# guangshan.net
KiCad netlist of a schematic drawn in EasyEDA Pro
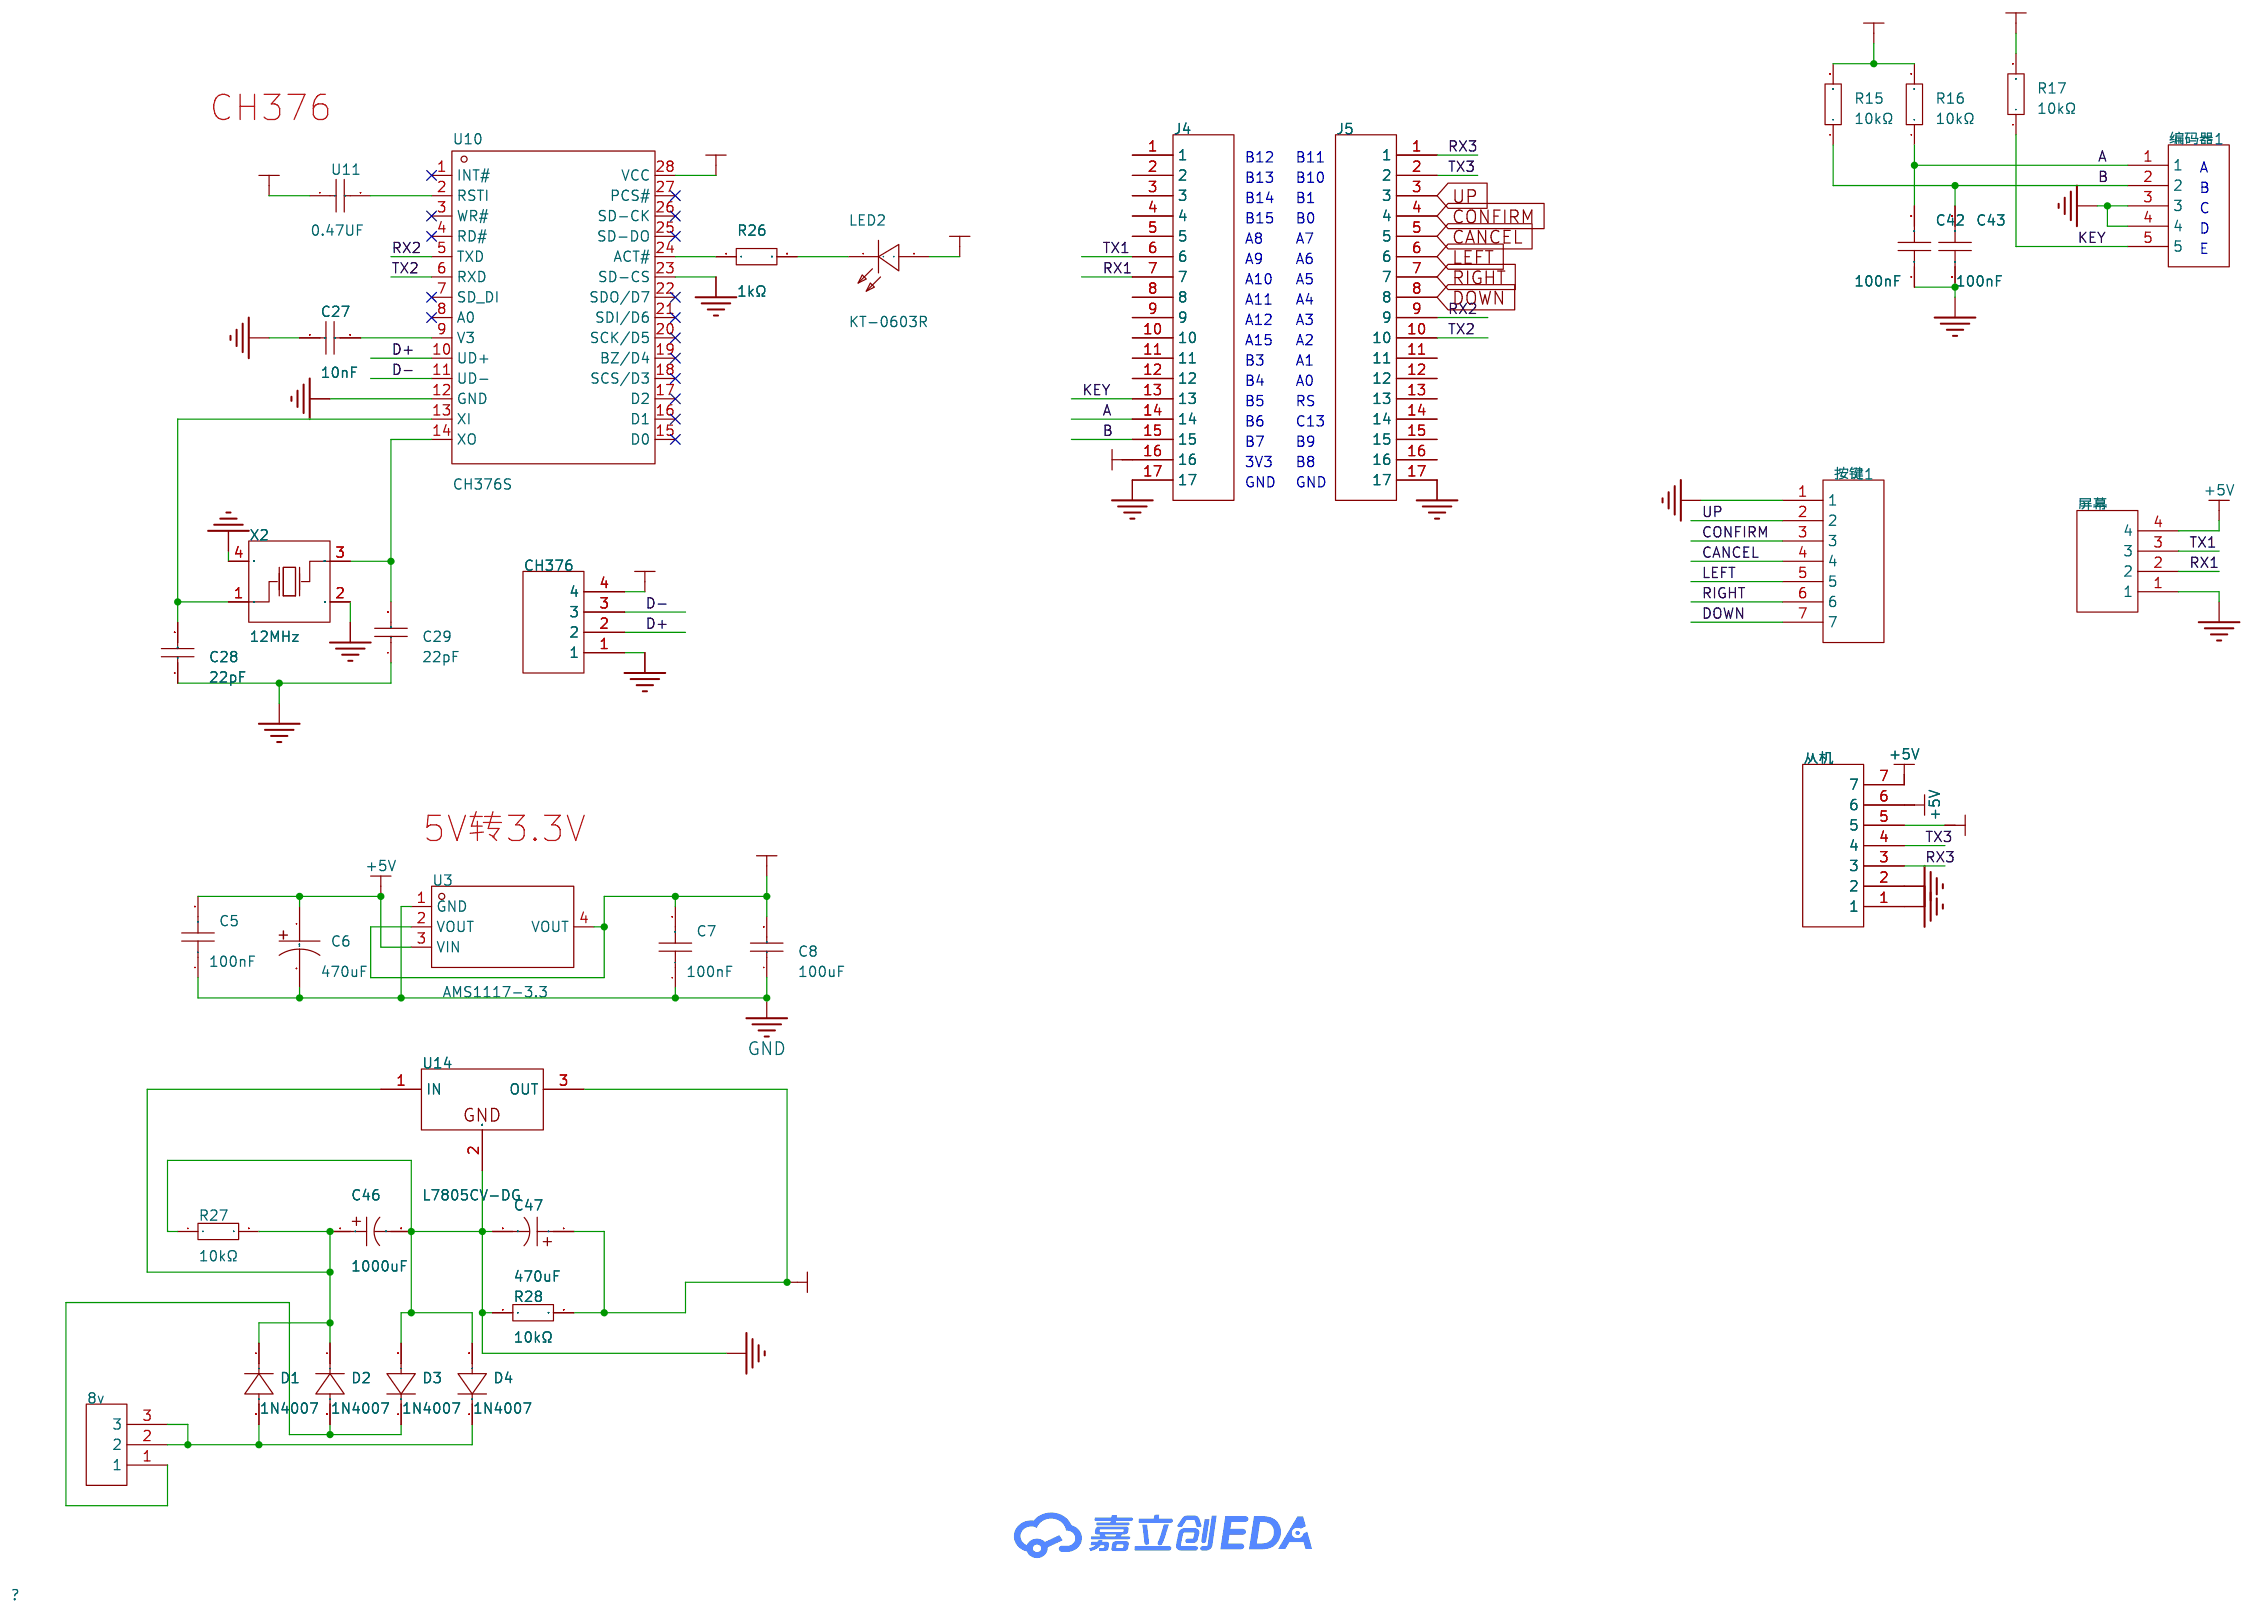
[diagram p0: schematic sheet]

(export (version "E")
  (design (tool "Eeschema 10.0.6"))
  (components
    (comp (ref "8v")
      (value "~")
      (footprint "easyedapro:CH2.54-3插座")
      (libsource (lib "easyedapro") (part "HDR-3P"))
    )
    (comp (ref "C5")
      (value "100nF")
      (footprint "easyedapro:C0603")
      (libsource (lib "easyedapro") (part "CapAcitance"))
    )
    (comp (ref "C6")
      (value "470uF")
      (footprint "easyedapro:CAP-SMD_BD6.3-L6.6-W6.6-FD")
      (description "容值:470uF;精度:±20%;额定电压:10V;纹波电流:200mA@120Hz;等效串联电阻:-;")
      (fields (field (name "Manufacturer Part") "RVT1A471M0607") (field (name "Manufacturer") "ROQANG(容强)"))
      (libsource (lib "easyedapro") (part "RVT1A471M0607_C335982"))
    )
    (comp (ref "C7")
      (value "100nF")
      (footprint "easyedapro:C0603")
      (libsource (lib "easyedapro") (part "CapAcitance"))
    )
    (comp (ref "C8")
      (value "100uF")
      (footprint "easyedapro:C1206")
      (description "容值:100uF;精度:±20%;额定电压:6.3V;材质(温度系数):X5R;")
      (fields
        (field (name "Manufacturer Part") "CL31A107MQHNNNE")
        (field (name "Manufacturer") "SAMSUNG(三星)")
      )
      (libsource (lib "easyedapro") (part "CL31A107MQHNNNE"))
    )
    (comp (ref "C27")
      (value "10nF")
      (footprint "easyedapro:C0603")
      (description "容值:10nF;精度:±10%;额定电压:50V;材质(温度系数):X7R;")
      (fields (field (name "Manufacturer Part") "0603B103K500NT") (field (name "Manufacturer") "FH(风华)"))
      (libsource (lib "easyedapro") (part "0603B103K500NT"))
    )
    (comp (ref "C28")
      (value "22pF")
      (footprint "easyedapro:C0603")
      (description "容值:22pF;精度:±5%;额定电压:50V;材质(温度系数):C0G;")
      (fields
        (field (name "Manufacturer Part") "CL10C220JB8NNNC")
        (field (name "Manufacturer") "SAMSUNG(三星)")
      )
      (libsource (lib "easyedapro") (part "CL10C220JB8NNNC"))
    )
    (comp (ref "C29")
      (value "22pF")
      (footprint "easyedapro:C0603")
      (description "容值:22pF;精度:±5%;额定电压:50V;材质(温度系数):C0G;")
      (fields
        (field (name "Manufacturer Part") "CL10C220JB8NNNC")
        (field (name "Manufacturer") "SAMSUNG(三星)")
      )
      (libsource (lib "easyedapro") (part "CL10C220JB8NNNC"))
    )
    (comp (ref "C42")
      (value "100nF")
      (footprint "easyedapro:C0402")
      (description "容值:100nF;精度:±10%;额定电压:50V;材质(温度系数):X7R;")
      (fields
        (field (name "Manufacturer Part") "CL05B104KB54PNC")
        (field (name "Manufacturer") "SAMSUNG(三星)")
      )
      (libsource (lib "easyedapro") (part "CL05B104KB54PNC"))
    )
    (comp (ref "C43")
      (value "100nF")
      (footprint "easyedapro:C0402")
      (description "容值:100nF;精度:±10%;额定电压:50V;材质(温度系数):X7R;")
      (fields
        (field (name "Manufacturer Part") "CL05B104KB54PNC")
        (field (name "Manufacturer") "SAMSUNG(三星)")
      )
      (libsource (lib "easyedapro") (part "CL05B104KB54PNC"))
    )
    (comp (ref "C46")
      (value "1000uF")
      (footprint "easyedapro:CAP-TH_BD10.0-P5.00-D0.6-FD")
      (description "容值:1000uF;额定电压:35V;")
      (fields
        (field (name "Manufacturer Part") "CD288108M1V1020VFL")
        (field (name "Manufacturer") "HRK(鸿瑞凯电子)")
      )
      (libsource (lib "easyedapro") (part "CD288108M1V1020VFL"))
    )
    (comp (ref "C47")
      (value "470uF")
      (footprint "easyedapro:CAP-TH_BD8.0-P3.50-D0.5-FD")
      (description "容值:470uF;精度:±20%;额定电压:16V;")
      (fields (field (name "Manufacturer Part") "16V470uF CD288") (field (name "Manufacturer") "HRK(鸿瑞凯电子)"))
      (libsource (lib "easyedapro") (part "16V470UF CD288"))
    )
    (comp (ref "CH376")
      (value "~")
      (footprint "easyedapro:CH2.54-4插座")
      (libsource (lib "easyedapro") (part "HDR-4P"))
    )
    (comp (ref "D1")
      (value "1N4007")
      (footprint "easyedapro:DO-41_BD2.4-L4.7-P8.70-D0.8-RD")
      (description "二极管配置:独立式;正向压降(Vf):1V@1A;直流反向耐压(Vr):1kV;整流电流:1A;")
      (fields (field (name "Manufacturer") "GOODWORK(固得沃克)"))
      (libsource (lib "easyedapro") (part "1N4007_C2985028"))
    )
    (comp (ref "D2")
      (value "1N4007")
      (footprint "easyedapro:DO-41_BD2.4-L4.7-P8.70-D0.8-RD")
      (description "二极管配置:独立式;正向压降(Vf):1V@1A;直流反向耐压(Vr):1kV;整流电流:1A;")
      (fields (field (name "Manufacturer") "GOODWORK(固得沃克)"))
      (libsource (lib "easyedapro") (part "1N4007_C2985028"))
    )
    (comp (ref "D3")
      (value "1N4007")
      (footprint "easyedapro:DO-41_BD2.4-L4.7-P8.70-D0.8-RD")
      (description "二极管配置:独立式;正向压降(Vf):1V@1A;直流反向耐压(Vr):1kV;整流电流:1A;")
      (fields (field (name "Manufacturer") "GOODWORK(固得沃克)"))
      (libsource (lib "easyedapro") (part "1N4007_C2985028"))
    )
    (comp (ref "D4")
      (value "1N4007")
      (footprint "easyedapro:DO-41_BD2.4-L4.7-P8.70-D0.8-RD")
      (description "二极管配置:独立式;正向压降(Vf):1V@1A;直流反向耐压(Vr):1kV;整流电流:1A;")
      (fields (field (name "Manufacturer") "GOODWORK(固得沃克)"))
      (libsource (lib "easyedapro") (part "1N4007_C2985028"))
    )
    (comp (ref "J4") (value "~") (libsource (lib "easyedapro") (part "HDR-17P")))
    (comp (ref "J5") (value "~") (libsource (lib "easyedapro") (part "HDR-17P")))
    (comp (ref "LED2")
      (value "KT-0603R")
      (footprint "easyedapro:LED0603-RD")
      (description "发光颜色:红色;功率:-;正向电流:-;主波长:-;二极管配置:-;透镜颜色:-;色温:-;发光角度:-;载带方式:-;工作温度:-40°C~+85°C;")
      (fields (field (name "Manufacturer") "KENTO"))
      (libsource (lib "easyedapro") (part "KT-0603R"))
    )
    (comp (ref "R15")
      (value "10kΩ")
      (footprint "easyedapro:R0805")
      (description "电阻类型:厚膜电阻;阻值:10kΩ;精度:±1%;功率:125mW;最大工作电压:150V;温度系数:±100ppm/°C;")
      (fields
        (field (name "Manufacturer Part") "0805W8F1002T5E")
        (field (name "Manufacturer") "UNI-ROYAL(厚声)")
      )
      (libsource (lib "easyedapro") (part "0805W8F1002T5E"))
    )
    (comp (ref "R16")
      (value "10kΩ")
      (footprint "easyedapro:R0805")
      (description "电阻类型:厚膜电阻;阻值:10kΩ;精度:±1%;功率:125mW;最大工作电压:150V;温度系数:±100ppm/°C;")
      (fields
        (field (name "Manufacturer Part") "0805W8F1002T5E")
        (field (name "Manufacturer") "UNI-ROYAL(厚声)")
      )
      (libsource (lib "easyedapro") (part "0805W8F1002T5E"))
    )
    (comp (ref "R17")
      (value "10kΩ")
      (footprint "easyedapro:R0805")
      (description "电阻类型:厚膜电阻;阻值:10kΩ;精度:±1%;功率:125mW;最大工作电压:150V;温度系数:±100ppm/°C;")
      (fields
        (field (name "Manufacturer Part") "0805W8F1002T5E")
        (field (name "Manufacturer") "UNI-ROYAL(厚声)")
      )
      (libsource (lib "easyedapro") (part "0805W8F1002T5E"))
    )
    (comp (ref "R26")
      (value "1kΩ")
      (footprint "easyedapro:R0603")
      (description "电阻类型:厚膜电阻;阻值:1kΩ;精度:±1%;功率:100mW;最大工作电压:75V;温度系数:±100ppm/°C;")
      (fields
        (field (name "Manufacturer Part") "0603WAF1001T5E")
        (field (name "Manufacturer") "UNI-ROYAL(厚声)")
      )
      (libsource (lib "easyedapro") (part "0603WAF1001T5E"))
    )
    (comp (ref "R27")
      (value "10kΩ")
      (footprint "easyedapro:R0603")
      (libsource (lib "easyedapro") (part "电阻"))
    )
    (comp (ref "R28")
      (value "10kΩ")
      (footprint "easyedapro:R0603")
      (libsource (lib "easyedapro") (part "电阻"))
    )
    (comp (ref "U3")
      (value "AMS1117-3.3")
      (footprint "easyedapro:SOT-223-3_L6.5-W3.4-P2.30-LS7.0-BR")
      (description "输出类型:固定;最大输入电压:-;输出电压:3.3V;最大输出电流:1A;电源纹波抑制比(PSRR):72dB@(120Hz);输出极性:正极;")
      (fields (field (name "Manufacturer") "AMS"))
      (libsource (lib "easyedapro") (part "AMS1117-3.3"))
    )
    (comp (ref "U10")
      (value "CH376S")
      (footprint "easyedapro:SOIC-28_L17.9-W7.5-P1.27-LS10.3-BL")
      (description "应用功能:-;接口协议:USB 2.0;数据速率:12Mbps;")
      (fields (field (name "Manufacturer") "WCH(南京沁恒)"))
      (libsource (lib "easyedapro") (part "CH376S"))
    )
    (comp (ref "U11")
      (value "0.47UF")
      (footprint "easyedapro:C0603")
      (libsource (lib "easyedapro") (part "CAPCER0.47UF25VX7R0603"))
    )
    (comp (ref "U14")
      (value "L7805CV-DG")
      (footprint "easyedapro:TO-220-3_L10.0-W4.5-P2.54-L")
      (description "输出类型:固定;最大输入电压:35V;输出电压:5V;输出电流:1.5A;电源纹波抑制比(PSRR):62dB@(120Hz);输出极性:正极;")
      (fields (field (name "Manufacturer") "ST(意法半导体)"))
      (libsource (lib "easyedapro") (part "L7805CV-DG"))
    )
    (comp (ref "X2")
      (value "12MHz")
      (footprint "easyedapro:CRYSTAL-SMD_4P-L3.2-W2.5-BL")
      (description "晶振类型:贴片晶振;频率:12MHz;常温频差:±10ppm;外接负载电容:20pF;频率稳定度(全温):±20ppm;")
      (fields (field (name "Manufacturer Part") "X322512MSB4SI") (field (name "Manufacturer") "YXC(扬兴晶振)"))
      (libsource (lib "easyedapro") (part "X322512MSB4SI"))
    )
    (comp (ref "从机")
      (value "~")
      (footprint "easyedapro:CH2.54-7插座")
      (libsource (lib "easyedapro") (part "HDR-7P"))
    )
    (comp (ref "屏幕")
      (value "~")
      (footprint "easyedapro:CH2.54-4插座")
      (libsource (lib "easyedapro") (part "HDR-4P"))
    )
    (comp (ref "按键1")
      (value "~")
      (footprint "easyedapro:CH2.54-7插座")
      (libsource (lib "easyedapro") (part "HDR-7P"))
    )
    (comp (ref "编码器1")
      (value "~")
      (footprint "easyedapro:CH2.54-5插座")
      (libsource (lib "easyedapro") (part "HDR-5P"))
    )
  )
  (nets
    (net (code "1") (name "+3V3") (class "Default")
      (node (ref "C7") (pin "2") (pinfunction "2_2") (pintype "input"))
      (node (ref "C8") (pin "2") (pinfunction "2_2") (pintype "input"))
      (node (ref "J4") (pin "16") (pinfunction "16_16") (pintype "input"))
      (node (ref "LED2") (pin "2") (pinfunction "A_2") (pintype "unspecified"))
      (node (ref "R15") (pin "2") (pinfunction "2_2") (pintype "input"))
      (node (ref "R16") (pin "2") (pinfunction "2_2") (pintype "input"))
      (node (ref "R17") (pin "2") (pinfunction "2_2") (pintype "input"))
      (node (ref "U10") (pin "28") (pinfunction "VCC_28") (pintype "unspecified"))
      (node (ref "U11") (pin "1") (pinfunction "1_1") (pintype "input"))
      (node (ref "U3") (pin "2") (pinfunction "VOUT_2") (pintype "unspecified"))
      (node (ref "U3") (pin "4") (pinfunction "VOUT_4") (pintype "unspecified"))
      (node (ref "从机") (pin "5") (pinfunction "5_5") (pintype "input"))
    )
    (net (code "2") (name "+5V") (class "Default")
      (node (ref "C47") (pin "1") (pinfunction "1_1") (pintype "input"))
      (node (ref "C5") (pin "2") (pinfunction "2_2") (pintype "input"))
      (node (ref "C6") (pin "1") (pinfunction "1_1") (pintype "unspecified"))
      (node (ref "CH376") (pin "4") (pinfunction "4_4") (pintype "input"))
      (node (ref "R28") (pin "2") (pinfunction "2_2") (pintype "input"))
      (node (ref "U14") (pin "3") (pinfunction "OUT_3") (pintype "unspecified"))
      (node (ref "U3") (pin "3") (pinfunction "VIN_3") (pintype "unspecified"))
      (node (ref "从机") (pin "6") (pinfunction "6_6") (pintype "input"))
      (node (ref "从机") (pin "7") (pinfunction "7_7") (pintype "input"))
      (node (ref "屏幕") (pin "4") (pinfunction "4_4") (pintype "input"))
    )
    (net (code "3") (name "/A") (class "Default")
      (node (ref "C42") (pin "2") (pinfunction "2_2") (pintype "input"))
      (node (ref "J4") (pin "14") (pinfunction "14_14") (pintype "input"))
      (node (ref "R16") (pin "1") (pinfunction "1_1") (pintype "input"))
      (node (ref "编码器1") (pin "1") (pinfunction "1_1") (pintype "input"))
    )
    (net (code "4") (name "/B") (class "Default")
      (node (ref "C43") (pin "2") (pinfunction "2_2") (pintype "input"))
      (node (ref "J4") (pin "15") (pinfunction "15_15") (pintype "input"))
      (node (ref "R15") (pin "1") (pinfunction "1_1") (pintype "input"))
      (node (ref "编码器1") (pin "2") (pinfunction "2_2") (pintype "input"))
    )
    (net (code "5") (name "/D+") (class "Default")
      (node (ref "CH376") (pin "2") (pinfunction "2_2") (pintype "input"))
      (node (ref "U10") (pin "10") (pinfunction "UD+_10") (pintype "unspecified"))
    )
    (net (code "6") (name "/D-") (class "Default")
      (node (ref "CH376") (pin "3") (pinfunction "3_3") (pintype "input"))
      (node (ref "U10") (pin "11") (pinfunction "UD-_11") (pintype "unspecified"))
    )
    (net (code "7") (name "/KEY") (class "Default")
      (node (ref "J4") (pin "13") (pinfunction "13_13") (pintype "input"))
      (node (ref "R17") (pin "1") (pinfunction "1_1") (pintype "input"))
      (node (ref "编码器1") (pin "5") (pinfunction "5_5") (pintype "input"))
    )
    (net (code "8") (name "/RX1") (class "Default")
      (node (ref "J4") (pin "7") (pinfunction "7_7") (pintype "input"))
      (node (ref "屏幕") (pin "2") (pinfunction "2_2") (pintype "input"))
    )
    (net (code "9") (name "/RX2") (class "Default")
      (node (ref "J5") (pin "9") (pinfunction "9_9") (pintype "input"))
      (node (ref "U10") (pin "5") (pinfunction "TXD_5") (pintype "unspecified"))
    )
    (net (code "10") (name "/RX3") (class "Default")
      (node (ref "J5") (pin "1") (pinfunction "1_1") (pintype "input"))
      (node (ref "从机") (pin "3") (pinfunction "3_3") (pintype "input"))
    )
    (net (code "11") (name "/TX1") (class "Default")
      (node (ref "J4") (pin "6") (pinfunction "6_6") (pintype "input"))
      (node (ref "屏幕") (pin "3") (pinfunction "3_3") (pintype "input"))
    )
    (net (code "12") (name "/TX2") (class "Default")
      (node (ref "J5") (pin "10") (pinfunction "10_10") (pintype "input"))
      (node (ref "U10") (pin "6") (pinfunction "RXD_6") (pintype "unspecified"))
    )
    (net (code "13") (name "/TX3") (class "Default")
      (node (ref "J5") (pin "2") (pinfunction "2_2") (pintype "input"))
      (node (ref "从机") (pin "4") (pinfunction "4_4") (pintype "input"))
    )
    (net (code "14") (name "CANCEL") (class "Default")
      (node (ref "J5") (pin "5") (pinfunction "5_5") (pintype "input"))
      (node (ref "按键1") (pin "4") (pinfunction "4_4") (pintype "input"))
    )
    (net (code "15") (name "CONFIRM") (class "Default")
      (node (ref "J5") (pin "4") (pinfunction "4_4") (pintype "input"))
      (node (ref "按键1") (pin "3") (pinfunction "3_3") (pintype "input"))
    )
    (net (code "16") (name "DOWN") (class "Default")
      (node (ref "J5") (pin "8") (pinfunction "8_8") (pintype "input"))
      (node (ref "按键1") (pin "7") (pinfunction "7_7") (pintype "input"))
    )
    (net (code "17") (name "GND") (class "Default")
      (node (ref "C27") (pin "1") (pinfunction "1_1") (pintype "input"))
      (node (ref "C28") (pin "1") (pinfunction "1_1") (pintype "input"))
      (node (ref "C29") (pin "1") (pinfunction "1_1") (pintype "input"))
      (node (ref "C42") (pin "1") (pinfunction "1_1") (pintype "input"))
      (node (ref "C43") (pin "1") (pinfunction "1_1") (pintype "input"))
      (node (ref "C46") (pin "2") (pinfunction "2_2") (pintype "input"))
      (node (ref "C47") (pin "2") (pinfunction "2_2") (pintype "input"))
      (node (ref "C5") (pin "1") (pinfunction "1_1") (pintype "input"))
      (node (ref "C6") (pin "2") (pinfunction "2_2") (pintype "unspecified"))
      (node (ref "C7") (pin "1") (pinfunction "1_1") (pintype "input"))
      (node (ref "C8") (pin "1") (pinfunction "1_1") (pintype "input"))
      (node (ref "CH376") (pin "1") (pinfunction "1_1") (pintype "input"))
      (node (ref "D3") (pin "2") (pinfunction "A_2") (pintype "unspecified"))
      (node (ref "D4") (pin "2") (pinfunction "A_2") (pintype "unspecified"))
      (node (ref "J4") (pin "17") (pinfunction "17_17") (pintype "input"))
      (node (ref "J5") (pin "17") (pinfunction "17_17") (pintype "input"))
      (node (ref "R27") (pin "1") (pinfunction "1_1") (pintype "input"))
      (node (ref "R28") (pin "1") (pinfunction "1_1") (pintype "input"))
      (node (ref "U10") (pin "12") (pinfunction "GND_12") (pintype "unspecified"))
      (node (ref "U10") (pin "23") (pinfunction "SD-CS_23") (pintype "unspecified"))
      (node (ref "U14") (pin "2") (pinfunction "GND_2") (pintype "unspecified"))
      (node (ref "U3") (pin "1") (pinfunction "GND_1") (pintype "unspecified"))
      (node (ref "X2") (pin "2") (pinfunction "GND_2") (pintype "unspecified"))
      (node (ref "X2") (pin "4") (pinfunction "GND_4") (pintype "unspecified"))
      (node (ref "从机") (pin "1") (pinfunction "1_1") (pintype "input"))
      (node (ref "从机") (pin "2") (pinfunction "2_2") (pintype "input"))
      (node (ref "屏幕") (pin "1") (pinfunction "1_1") (pintype "input"))
      (node (ref "按键1") (pin "1") (pinfunction "1_1") (pintype "input"))
      (node (ref "编码器1") (pin "3") (pinfunction "3_3") (pintype "input"))
      (node (ref "编码器1") (pin "4") (pinfunction "4_4") (pintype "input"))
    )
    (net (code "18") (name "LEFT") (class "Default")
      (node (ref "J5") (pin "6") (pinfunction "6_6") (pintype "input"))
      (node (ref "按键1") (pin "5") (pinfunction "5_5") (pintype "input"))
    )
    (net (code "19") (name "Net-(D1-A)") (class "Default")
      (node (ref "8v") (pin "2") (pinfunction "2_2") (pintype "input"))
      (node (ref "8v") (pin "3") (pinfunction "3_3") (pintype "input"))
      (node (ref "D1") (pin "2") (pinfunction "A_2") (pintype "unspecified"))
      (node (ref "D4") (pin "1") (pinfunction "K_1") (pintype "unspecified"))
    )
    (net (code "20") (name "Net-(D1-K)") (class "Default")
      (node (ref "C46") (pin "1") (pinfunction "1_1") (pintype "input"))
      (node (ref "D1") (pin "1") (pinfunction "K_1") (pintype "unspecified"))
      (node (ref "D2") (pin "1") (pinfunction "K_1") (pintype "unspecified"))
      (node (ref "R27") (pin "2") (pinfunction "2_2") (pintype "input"))
      (node (ref "U14") (pin "1") (pinfunction "IN_1") (pintype "unspecified"))
    )
    (net (code "21") (name "Net-(D2-A)") (class "Default")
      (node (ref "8v") (pin "1") (pinfunction "1_1") (pintype "input"))
      (node (ref "D2") (pin "2") (pinfunction "A_2") (pintype "unspecified"))
      (node (ref "D3") (pin "1") (pinfunction "K_1") (pintype "unspecified"))
    )
    (net (code "22") (name "Net-(LED2-K)") (class "Default")
      (node (ref "LED2") (pin "1") (pinfunction "K_1") (pintype "unspecified"))
      (node (ref "R26") (pin "2") (pinfunction "2_2") (pintype "input"))
    )
    (net (code "23") (name "Net-(U10-ACT#)") (class "Default")
      (node (ref "R26") (pin "1") (pinfunction "1_1") (pintype "input"))
      (node (ref "U10") (pin "24") (pinfunction "ACT#_24") (pintype "unspecified"))
    )
    (net (code "24") (name "Net-(U10-RSTI)") (class "Default")
      (node (ref "U10") (pin "2") (pinfunction "RSTI_2") (pintype "unspecified"))
      (node (ref "U11") (pin "2") (pinfunction "2_2") (pintype "input"))
    )
    (net (code "25") (name "Net-(U10-V3)") (class "Default")
      (node (ref "C27") (pin "2") (pinfunction "2_2") (pintype "input"))
      (node (ref "U10") (pin "9") (pinfunction "V3_9") (pintype "unspecified"))
    )
    (net (code "26") (name "Net-(U10-XI)") (class "Default")
      (node (ref "C28") (pin "2") (pinfunction "2_2") (pintype "input"))
      (node (ref "U10") (pin "13") (pinfunction "XI_13") (pintype "unspecified"))
      (node (ref "X2") (pin "1") (pinfunction "OSC1_1") (pintype "unspecified"))
    )
    (net (code "27") (name "Net-(U10-XO)") (class "Default")
      (node (ref "C29") (pin "2") (pinfunction "2_2") (pintype "input"))
      (node (ref "U10") (pin "14") (pinfunction "XO_14") (pintype "unspecified"))
      (node (ref "X2") (pin "3") (pinfunction "OSC2_3") (pintype "unspecified"))
    )
    (net (code "28") (name "RIGHT") (class "Default")
      (node (ref "J5") (pin "7") (pinfunction "7_7") (pintype "input"))
      (node (ref "按键1") (pin "6") (pinfunction "6_6") (pintype "input"))
    )
    (net (code "29") (name "UP") (class "Default")
      (node (ref "J5") (pin "3") (pinfunction "3_3") (pintype "input"))
      (node (ref "按键1") (pin "2") (pinfunction "2_2") (pintype "input"))
    )
    (net (code "30") (name "unconnected-(J4-Pad1)") (class "Default")
      (node (ref "J4") (pin "1") (pinfunction "1_1") (pintype "input"))
    )
    (net (code "31") (name "unconnected-(J4-Pad2)") (class "Default")
      (node (ref "J4") (pin "2") (pinfunction "2_2") (pintype "input"))
    )
    (net (code "32") (name "unconnected-(J4-Pad3)") (class "Default")
      (node (ref "J4") (pin "3") (pinfunction "3_3") (pintype "input"))
    )
    (net (code "33") (name "unconnected-(J4-Pad4)") (class "Default")
      (node (ref "J4") (pin "4") (pinfunction "4_4") (pintype "input"))
    )
    (net (code "34") (name "unconnected-(J4-Pad5)") (class "Default")
      (node (ref "J4") (pin "5") (pinfunction "5_5") (pintype "input"))
    )
    (net (code "35") (name "unconnected-(J4-Pad8)") (class "Default")
      (node (ref "J4") (pin "8") (pinfunction "8_8") (pintype "input"))
    )
    (net (code "36") (name "unconnected-(J4-Pad9)") (class "Default")
      (node (ref "J4") (pin "9") (pinfunction "9_9") (pintype "input"))
    )
    (net (code "37") (name "unconnected-(J4-Pad10)") (class "Default")
      (node (ref "J4") (pin "10") (pinfunction "10_10") (pintype "input"))
    )
    (net (code "38") (name "unconnected-(J4-Pad11)") (class "Default")
      (node (ref "J4") (pin "11") (pinfunction "11_11") (pintype "input"))
    )
    (net (code "39") (name "unconnected-(J4-Pad12)") (class "Default")
      (node (ref "J4") (pin "12") (pinfunction "12_12") (pintype "input"))
    )
    (net (code "40") (name "unconnected-(J5-Pad11)") (class "Default")
      (node (ref "J5") (pin "11") (pinfunction "11_11") (pintype "input"))
    )
    (net (code "41") (name "unconnected-(J5-Pad12)") (class "Default")
      (node (ref "J5") (pin "12") (pinfunction "12_12") (pintype "input"))
    )
    (net (code "42") (name "unconnected-(J5-Pad13)") (class "Default")
      (node (ref "J5") (pin "13") (pinfunction "13_13") (pintype "input"))
    )
    (net (code "43") (name "unconnected-(J5-Pad14)") (class "Default")
      (node (ref "J5") (pin "14") (pinfunction "14_14") (pintype "input"))
    )
    (net (code "44") (name "unconnected-(J5-Pad15)") (class "Default")
      (node (ref "J5") (pin "15") (pinfunction "15_15") (pintype "input"))
    )
    (net (code "45") (name "unconnected-(J5-Pad16)") (class "Default")
      (node (ref "J5") (pin "16") (pinfunction "16_16") (pintype "input"))
    )
    (net (code "46") (name "unconnected-(U10-A0-Pad8)") (class "Default")
      (node (ref "U10") (pin "8") (pinfunction "A0_8") (pintype "unspecified+no_connect"))
    )
    (net (code "47") (name "unconnected-(U10-BZ{slash}D4-Pad19)") (class "Default")
      (node (ref "U10") (pin "19") (pinfunction "BZ/D4_19") (pintype "unspecified+no_connect"))
    )
    (net (code "48") (name "unconnected-(U10-D0-Pad15)") (class "Default")
      (node (ref "U10") (pin "15") (pinfunction "D0_15") (pintype "unspecified+no_connect"))
    )
    (net (code "49") (name "unconnected-(U10-D1-Pad16)") (class "Default")
      (node (ref "U10") (pin "16") (pinfunction "D1_16") (pintype "unspecified+no_connect"))
    )
    (net (code "50") (name "unconnected-(U10-D2-Pad17)") (class "Default")
      (node (ref "U10") (pin "17") (pinfunction "D2_17") (pintype "unspecified+no_connect"))
    )
    (net (code "51") (name "unconnected-(U10-INT#-Pad1)") (class "Default")
      (node (ref "U10") (pin "1") (pinfunction "INT#_1") (pintype "unspecified+no_connect"))
    )
    (net (code "52") (name "unconnected-(U10-PCS#-Pad27)") (class "Default")
      (node (ref "U10") (pin "27") (pinfunction "PCS#_27") (pintype "unspecified+no_connect"))
    )
    (net (code "53") (name "unconnected-(U10-RD#-Pad4)") (class "Default")
      (node (ref "U10") (pin "4") (pinfunction "RD#_4") (pintype "unspecified+no_connect"))
    )
    (net (code "54") (name "unconnected-(U10-SCK{slash}D5-Pad20)") (class "Default")
      (node (ref "U10") (pin "20") (pinfunction "SCK/D5_20") (pintype "unspecified+no_connect"))
    )
    (net (code "55") (name "unconnected-(U10-SCS{slash}D3-Pad18)") (class "Default")
      (node (ref "U10") (pin "18") (pinfunction "SCS/D3_18") (pintype "unspecified+no_connect"))
    )
    (net (code "56") (name "unconnected-(U10-SD-CK-Pad26)") (class "Default")
      (node (ref "U10") (pin "26") (pinfunction "SD-CK_26") (pintype "unspecified+no_connect"))
    )
    (net (code "57") (name "unconnected-(U10-SD-DO-Pad25)") (class "Default")
      (node (ref "U10") (pin "25") (pinfunction "SD-DO_25") (pintype "unspecified+no_connect"))
    )
    (net (code "58") (name "unconnected-(U10-SDI{slash}D6-Pad21)") (class "Default")
      (node (ref "U10") (pin "21") (pinfunction "SDI/D6_21") (pintype "unspecified+no_connect"))
    )
    (net (code "59") (name "unconnected-(U10-SDO{slash}D7-Pad22)") (class "Default")
      (node (ref "U10") (pin "22") (pinfunction "SDO/D7_22") (pintype "unspecified+no_connect"))
    )
    (net (code "60") (name "unconnected-(U10-SD_DI-Pad7)") (class "Default")
      (node (ref "U10") (pin "7") (pinfunction "SD_DI_7") (pintype "unspecified+no_connect"))
    )
    (net (code "61") (name "unconnected-(U10-WR#-Pad3)") (class "Default")
      (node (ref "U10") (pin "3") (pinfunction "WR#_3") (pintype "unspecified+no_connect"))
    )
  )
)
